# RFMXX.net
KiCad netlist of a schematic drawn in EAGLE
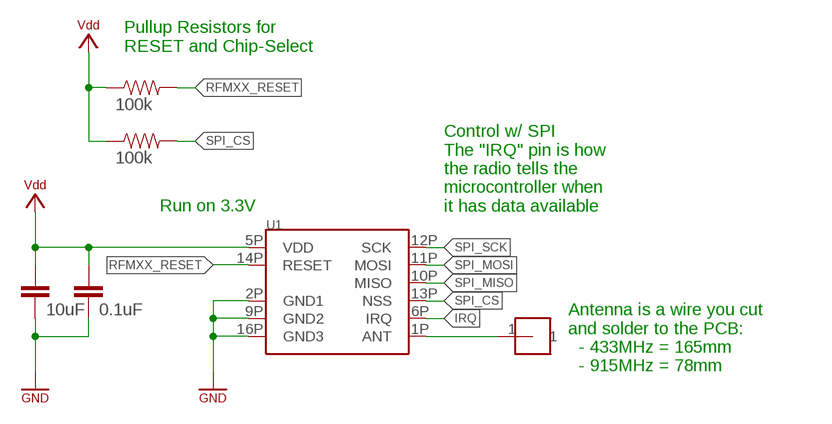
[diagram p0: schematic, sheet 1]

(export (version "E")
  (design (tool "Eeschema 10.0.6"))
  (components
    (comp (ref "C1")
      (value "10uF")
      (footprint "eagle-import:0805")
      (libsource (lib "eagle-import") (part "COMPONENT_CAP-0805"))
    )
    (comp (ref "C2")
      (value "0.1uF")
      (footprint "eagle-import:0805")
      (libsource (lib "eagle-import") (part "COMPONENT_CAP-0805"))
    )
    (comp (ref "R1")
      (value "100k")
      (footprint "eagle-import:0805")
      (libsource (lib "eagle-import") (part "COMPONENT_RESISTOR-0805"))
    )
    (comp (ref "R2")
      (value "100k")
      (footprint "eagle-import:0805")
      (libsource (lib "eagle-import") (part "COMPONENT_RESISTOR-0805"))
    )
    (comp (ref "U$1")
      (value "HEADER-1-DIP")
      (footprint "eagle-import:HEADER-1-DIP")
      (libsource (lib "eagle-import") (part "HEADER-1-DIP"))
    )
    (comp (ref "U1")
      (value "RADIO_RFMXX_SMT")
      (footprint "eagle-import:RFMXX_SMT")
      (libsource (lib "eagle-import") (part "RADIO_RFMXX_SMT"))
    )
  )
  (nets
    (net (code "1") (name "IRQ") (class "Default")
      (node (ref "U1") (pin "6P") (pinfunction "IRQ_6P") (pintype "input"))
    )
    (net (code "2") (name "Net-(U1-ANT)") (class "Default")
      (node (ref "U$1") (pin "1") (pinfunction "1_1") (pintype "bidirectional"))
      (node (ref "U1") (pin "1P") (pinfunction "ANT_1P") (pintype "bidirectional"))
    )
    (net (code "3") (name "RFMXX_RESET") (class "Default")
      (node (ref "R2") (pin "2") (pinfunction "2_2") (pintype "passive"))
      (node (ref "U1") (pin "14P") (pinfunction "RESET_14P") (pintype "input"))
    )
    (net (code "4") (name "SPI_CS") (class "Default")
      (node (ref "R1") (pin "2") (pinfunction "2_2") (pintype "passive"))
      (node (ref "U1") (pin "13P") (pinfunction "NSS_13P") (pintype "input"))
    )
    (net (code "5") (name "SPI_MISO") (class "Default")
      (node (ref "U1") (pin "10P") (pinfunction "MISO_10P") (pintype "output"))
    )
    (net (code "6") (name "SPI_MOSI") (class "Default")
      (node (ref "U1") (pin "11P") (pinfunction "MOSI_11P") (pintype "input"))
    )
    (net (code "7") (name "SPI_SCK") (class "Default")
      (node (ref "U1") (pin "12P") (pinfunction "SCK_12P") (pintype "input"))
    )
    (net (code "8") (name "SYMBOL_GND") (class "Default")
      (node (ref "C1") (pin "2") (pinfunction "2_2") (pintype "passive"))
      (node (ref "C2") (pin "2") (pinfunction "2_2") (pintype "passive"))
      (node (ref "U1") (pin "16P") (pinfunction "GND3_16P") (pintype "power_in"))
      (node (ref "U1") (pin "2P") (pinfunction "GND1_2P") (pintype "power_in"))
      (node (ref "U1") (pin "9P") (pinfunction "GND2_9P") (pintype "power_in"))
    )
    (net (code "9") (name "SYMBOL_VDD") (class "Default")
      (node (ref "C1") (pin "1") (pinfunction "1_1") (pintype "passive"))
      (node (ref "C2") (pin "1") (pinfunction "1_1") (pintype "passive"))
      (node (ref "R1") (pin "1") (pinfunction "1_1") (pintype "passive"))
      (node (ref "R2") (pin "1") (pinfunction "1_1") (pintype "passive"))
      (node (ref "U1") (pin "5P") (pinfunction "VDD_5P") (pintype "power_in"))
    )
  )
)
